# driver_V1_2.net
KiCad netlist of a schematic drawn in Altium Designer
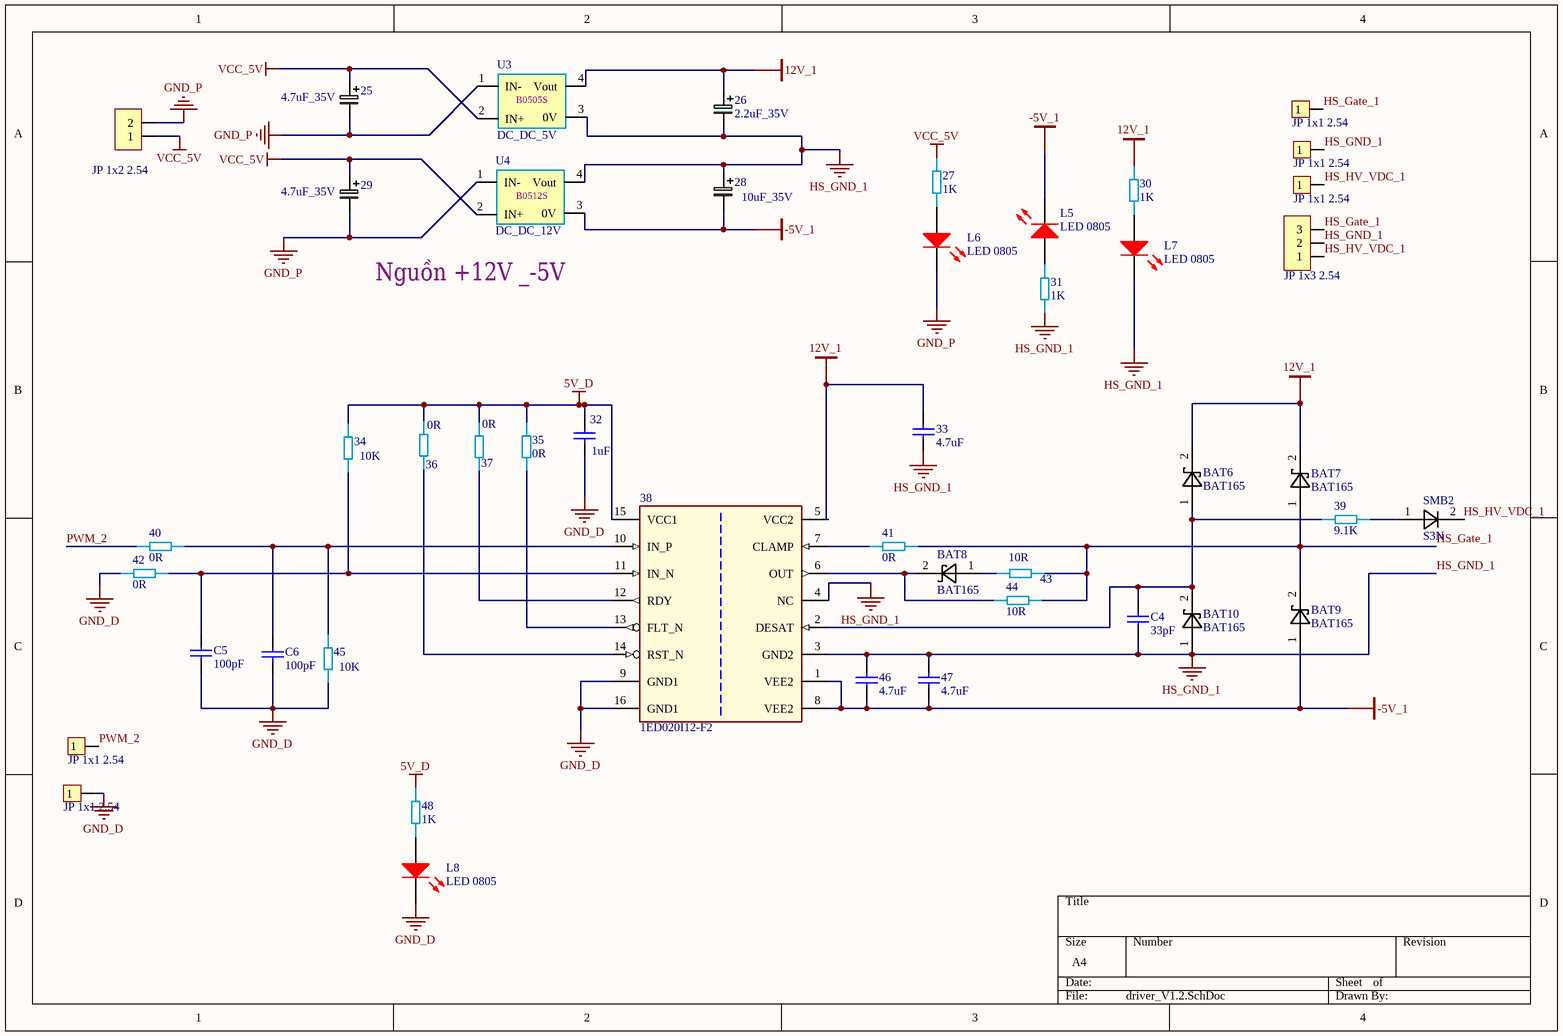
[diagram p0: driver_V1.2.SchDoc]

(export (version "E")
  (design (tool "Eeschema 10.0.6"))
  (components
    (comp (ref "25")
      (value "4.7uF_35V")
      (footprint "tu_4x5.4mm")
      (description "capacitor_electric")
      (libsource (lib "labari_altium1") (part "capacitor_electric"))
    )
    (comp (ref "26")
      (value "2.2uF_35V")
      (footprint "tu_4x5.4mm")
      (description "capacitor_electric")
      (libsource (lib "labari_altium1") (part "capacitor_electric"))
    )
    (comp (ref "27")
      (value "1K")
      (footprint "RES1206")
      (libsource (lib "labari_altium1") (part "311-0.0GRTR-ND"))
    )
    (comp (ref "28")
      (value "10uF_35V")
      (footprint "tu_4x5.4mm")
      (description "capacitor_electric")
      (libsource (lib "labari_altium1") (part "capacitor_electric"))
    )
    (comp (ref "29")
      (value "4.7uF_35V")
      (footprint "tu_4x5.4mm")
      (description "capacitor_electric")
      (libsource (lib "labari_altium1") (part "capacitor_electric"))
    )
    (comp (ref "30")
      (value "1K")
      (footprint "RES1206")
      (libsource (lib "labari_altium1") (part "311-0.0GRTR-ND"))
    )
    (comp (ref "31")
      (value "1K")
      (footprint "RES1206")
      (libsource (lib "labari_altium1") (part "311-0.0GRTR-ND"))
    )
    (comp (ref "32")
      (value "1uF")
      (footprint "Tu 0805_N")
      (libsource (lib "labari_altium1") (part "cap_0805"))
    )
    (comp (ref "33")
      (value "4.7uF")
      (footprint "tu 1206_N")
      (libsource (lib "labari_altium1") (part "cap_1210"))
    )
    (comp (ref "34")
      (value "10K")
      (footprint "RES1206")
      (libsource (lib "labari_altium1") (part "311-0.0GRTR-ND"))
    )
    (comp (ref "35")
      (value "0R")
      (footprint "RES1206")
      (libsource (lib "labari_altium1") (part "311-0.0GRTR-ND"))
    )
    (comp (ref "36")
      (value "0R")
      (footprint "RES1206")
      (libsource (lib "labari_altium1") (part "311-0.0GRTR-ND"))
    )
    (comp (ref "37")
      (value "0R")
      (footprint "RES1206")
      (libsource (lib "labari_altium1") (part "311-0.0GRTR-ND"))
    )
    (comp (ref "38")
      (value "1ED020I12-F2")
      (footprint "SOIC127P1028X264-16N-1")
      (description "Single IGBT Driver IC")
      (fields (field (name "MANUFACTURER") "Infineon Technologies"))
      (libsource (lib "labari_altium1") (part "1ED020I12-F2"))
    )
    (comp (ref "39")
      (value "9.1K")
      (footprint "RES_2512")
      (libsource (lib "labari_altium1") (part "311-0.0GRTR-ND"))
    )
    (comp (ref "40")
      (value "0R")
      (footprint "RES1206")
      (libsource (lib "labari_altium1") (part "311-0.0GRTR-ND"))
    )
    (comp (ref "41")
      (value "0R")
      (footprint "RES_2512")
      (libsource (lib "labari_altium1") (part "311-0.0GRTR-ND"))
    )
    (comp (ref "42")
      (value "0R")
      (footprint "RES1206")
      (libsource (lib "labari_altium1") (part "311-0.0GRTR-ND"))
    )
    (comp (ref "43")
      (value "10R")
      (footprint "RES_2512")
      (libsource (lib "labari_altium1") (part "311-0.0GRTR-ND"))
    )
    (comp (ref "44")
      (value "10R")
      (footprint "RES_2512")
      (libsource (lib "labari_altium1") (part "311-0.0GRTR-ND"))
    )
    (comp (ref "45")
      (value "10K")
      (footprint "RES1206")
      (libsource (lib "labari_altium1") (part "311-0.0GRTR-ND"))
    )
    (comp (ref "46")
      (value "4.7uF")
      (footprint "tu 1206_N")
      (libsource (lib "labari_altium1") (part "cap_1210"))
    )
    (comp (ref "47")
      (value "4.7uF")
      (footprint "tu 1206_N")
      (libsource (lib "labari_altium1") (part "cap_1210"))
    )
    (comp (ref "48")
      (value "1K")
      (footprint "RES1206")
      (libsource (lib "labari_altium1") (part "311-0.0GRTR-ND"))
    )
    (comp (ref "BAT6") (value "BAT165") (footprint "SMB") (libsource (lib "labari_altium1") (part "BAT165")))
    (comp (ref "BAT7") (value "BAT165") (footprint "SMB") (libsource (lib "labari_altium1") (part "BAT165")))
    (comp (ref "BAT8") (value "BAT165") (footprint "SMB") (libsource (lib "labari_altium1") (part "BAT165")))
    (comp (ref "BAT9") (value "BAT165") (footprint "SMB") (libsource (lib "labari_altium1") (part "BAT165")))
    (comp (ref "BAT10") (value "BAT165") (footprint "SMB") (libsource (lib "labari_altium1") (part "BAT165")))
    (comp (ref "C4")
      (value "33pF")
      (footprint "Tu 0805_N")
      (libsource (lib "labari_altium1") (part "cap_0805"))
    )
    (comp (ref "C5")
      (value "100pF")
      (footprint "Tu 0805_N")
      (libsource (lib "labari_altium1") (part "cap_0805"))
    )
    (comp (ref "C6")
      (value "100pF")
      (footprint "Tu 0805_N")
      (libsource (lib "labari_altium1") (part "cap_0805"))
    )
    (comp (ref "JP9")
      (value "JP 1x1 2.54")
      (footprint "test_point")
      (description "Cắm")
      (libsource (lib "labari_altium1") (part "JP 1x1 2.54 Duc Thang"))
    )
    (comp (ref "JP10")
      (value "JP 1x2 2.54")
      (footprint "JP 1x2 DT_n")
      (description "Cắm")
      (libsource (lib "labari_altium1") (part "JP 1x2 2.54 Duc Thang"))
    )
    (comp (ref "JP11")
      (value "JP 1x1 2.54")
      (footprint "test_point")
      (description "Cắm")
      (libsource (lib "labari_altium1") (part "JP 1x1 2.54 Duc Thang"))
    )
    (comp (ref "JP12")
      (value "JP 1x1 2.54")
      (footprint "test_point")
      (description "Cắm")
      (libsource (lib "labari_altium1") (part "JP 1x1 2.54 Duc Thang"))
    )
    (comp (ref "JP13")
      (value "JP 1x3 2.54")
      (footprint "XH2.54M-3")
      (description "Cắm")
      (libsource (lib "labari_altium1") (part "JP 1x3 2.54 Duc Cong"))
    )
    (comp (ref "JP14")
      (value "JP 1x1 2.54")
      (footprint "test_point")
      (description "Cắm")
      (libsource (lib "labari_altium1") (part "JP 1x1 2.54 Duc Thang"))
    )
    (comp (ref "JP15")
      (value "JP 1x1 2.54")
      (footprint "test_point")
      (description "Cắm")
      (libsource (lib "labari_altium1") (part "JP 1x1 2.54 Duc Thang"))
    )
    (comp (ref "L5")
      (value "LED 0805")
      (footprint "LED-0805-Red")
      (description "Dán")
      (libsource (lib "labari_altium1") (part "LED 0805 Do"))
    )
    (comp (ref "L6")
      (value "LED 0805")
      (footprint "LED-0805-Red")
      (description "Dán")
      (libsource (lib "labari_altium1") (part "LED 0805 Do"))
    )
    (comp (ref "L7")
      (value "LED 0805")
      (footprint "LED-0805-Red")
      (description "Dán")
      (libsource (lib "labari_altium1") (part "LED 0805 Do"))
    )
    (comp (ref "L8")
      (value "LED 0805")
      (footprint "LED-0805-Red")
      (description "Dán")
      (libsource (lib "labari_altium1") (part "LED 0805 Do"))
    )
    (comp (ref "SMB2") (value "S3N") (footprint "SMB") (libsource (lib "labari_altium1") (part "S3A-S3N")))
    (comp (ref "U3")
      (value "DC_DC_5V")
      (footprint "B0505S/D-1W")
      (libsource (lib "labari_altium1") (part "DC_DC_5v"))
    )
    (comp (ref "U4")
      (value "DC_DC_12V")
      (footprint "B0512S/D-1W")
      (libsource (lib "labari_altium1") (part "DC_DC_12v"))
    )
  )
  (nets
    (net (code "1") (name "-5V_1") (class "Default")
      (node (ref "28") (pin "2") (pinfunction "2_2") (pintype "passive"))
      (node (ref "38") (pin "1") (pinfunction "VEE2_1") (pintype "power_in"))
      (node (ref "38") (pin "8") (pinfunction "VEE2_8") (pintype "power_in"))
      (node (ref "46") (pin "1") (pinfunction "1_1") (pintype "passive"))
      (node (ref "47") (pin "1") (pinfunction "1_1") (pintype "passive"))
      (node (ref "BAT9") (pin "1") (pinfunction "1_1") (pintype "passive"))
      (node (ref "L5") (pin "2") (pinfunction "K_2") (pintype "passive"))
      (node (ref "U4") (pin "3") (pinfunction "0V_3") (pintype "passive"))
    )
    (net (code "2") (name "/HS_Gate_1") (class "Default")
      (node (ref "41") (pin "2") (pinfunction "2_2") (pintype "passive"))
      (node (ref "43") (pin "2") (pinfunction "2_2") (pintype "passive"))
      (node (ref "44") (pin "2") (pinfunction "2_2") (pintype "passive"))
      (node (ref "BAT7") (pin "1") (pinfunction "1_1") (pintype "passive"))
      (node (ref "BAT9") (pin "2") (pinfunction "2_2") (pintype "passive"))
      (node (ref "JP13") (pin "3") (pinfunction "3_3") (pintype "passive"))
      (node (ref "JP9") (pin "1") (pinfunction "1_1") (pintype "passive"))
    )
    (net (code "3") (name "/HS_HV_VDC_1") (class "Default")
      (node (ref "JP12") (pin "1") (pinfunction "1_1") (pintype "passive"))
      (node (ref "JP13") (pin "1") (pinfunction "1_1") (pintype "passive"))
      (node (ref "SMB2") (pin "2") (pinfunction "2_2") (pintype "passive"))
    )
    (net (code "4") (name "/PWM_2") (class "Default")
      (node (ref "40") (pin "2") (pinfunction "2_2") (pintype "passive"))
      (node (ref "JP14") (pin "1") (pinfunction "1_1") (pintype "passive"))
    )
    (net (code "5") (name "5V_D") (class "Default")
      (node (ref "32") (pin "2") (pinfunction "2_2") (pintype "passive"))
      (node (ref "34") (pin "2") (pinfunction "2_2") (pintype "passive"))
      (node (ref "35") (pin "1") (pinfunction "1_1") (pintype "passive"))
      (node (ref "36") (pin "2") (pinfunction "2_2") (pintype "passive"))
      (node (ref "37") (pin "1") (pinfunction "1_1") (pintype "passive"))
      (node (ref "38") (pin "15") (pinfunction "VCC1_15") (pintype "power_in"))
      (node (ref "48") (pin "1") (pinfunction "1_1") (pintype "passive"))
    )
    (net (code "6") (name "12V_1") (class "Default")
      (node (ref "26") (pin "1") (pinfunction "1_1") (pintype "passive"))
      (node (ref "30") (pin "1") (pinfunction "1_1") (pintype "passive"))
      (node (ref "33") (pin "2") (pinfunction "2_2") (pintype "passive"))
      (node (ref "38") (pin "5") (pinfunction "VCC2_5") (pintype "power_in"))
      (node (ref "BAT6") (pin "2") (pinfunction "2_2") (pintype "passive"))
      (node (ref "BAT7") (pin "2") (pinfunction "2_2") (pintype "passive"))
      (node (ref "U3") (pin "4") (pinfunction "Vout_4") (pintype "passive"))
    )
    (net (code "7") (name "GND_D") (class "Default")
      (node (ref "32") (pin "1") (pinfunction "1_1") (pintype "passive"))
      (node (ref "38") (pin "16") (pinfunction "GND1_16") (pintype "power_in"))
      (node (ref "38") (pin "9") (pinfunction "GND1_9") (pintype "power_in"))
      (node (ref "42") (pin "2") (pinfunction "2_2") (pintype "passive"))
      (node (ref "45") (pin "1") (pinfunction "1_1") (pintype "passive"))
      (node (ref "C5") (pin "1") (pinfunction "1_1") (pintype "passive"))
      (node (ref "C6") (pin "1") (pinfunction "1_1") (pintype "passive"))
      (node (ref "JP15") (pin "1") (pinfunction "1_1") (pintype "passive"))
      (node (ref "L8") (pin "2") (pinfunction "K_2") (pintype "passive"))
    )
    (net (code "8") (name "GND_P") (class "Default")
      (node (ref "25") (pin "2") (pinfunction "2_2") (pintype "passive"))
      (node (ref "29") (pin "2") (pinfunction "2_2") (pintype "passive"))
      (node (ref "JP10") (pin "2") (pinfunction "2_2") (pintype "passive"))
      (node (ref "L6") (pin "2") (pinfunction "K_2") (pintype "passive"))
      (node (ref "U3") (pin "1") (pinfunction "IN-_1") (pintype "passive"))
      (node (ref "U4") (pin "1") (pinfunction "IN-_1") (pintype "passive"))
    )
    (net (code "9") (name "HS_GND_1") (class "Default")
      (node (ref "26") (pin "2") (pinfunction "2_2") (pintype "passive"))
      (node (ref "28") (pin "1") (pinfunction "1_1") (pintype "passive"))
      (node (ref "31") (pin "2") (pinfunction "2_2") (pintype "passive"))
      (node (ref "33") (pin "1") (pinfunction "1_1") (pintype "passive"))
      (node (ref "38") (pin "3") (pinfunction "GND2_3") (pintype "power_in"))
      (node (ref "38") (pin "4") (pinfunction "NC_4") (pintype "passive"))
      (node (ref "46") (pin "2") (pinfunction "2_2") (pintype "passive"))
      (node (ref "47") (pin "2") (pinfunction "2_2") (pintype "passive"))
      (node (ref "BAT10") (pin "1") (pinfunction "1_1") (pintype "passive"))
      (node (ref "C4") (pin "1") (pinfunction "1_1") (pintype "passive"))
      (node (ref "JP11") (pin "1") (pinfunction "1_1") (pintype "passive"))
      (node (ref "JP13") (pin "2") (pinfunction "2_2") (pintype "passive"))
      (node (ref "L7") (pin "2") (pinfunction "K_2") (pintype "passive"))
      (node (ref "U3") (pin "3") (pinfunction "0V_3") (pintype "passive"))
      (node (ref "U4") (pin "4") (pinfunction "Vout_4") (pintype "passive"))
    )
    (net (code "10") (name "Net-(38-CLAMP)") (class "Default")
      (node (ref "38") (pin "7") (pinfunction "CLAMP_7") (pintype "input"))
      (node (ref "41") (pin "1") (pinfunction "1_1") (pintype "passive"))
    )
    (net (code "11") (name "Net-(38-DESAT)") (class "Default")
      (node (ref "38") (pin "2") (pinfunction "DESAT_2") (pintype "input"))
      (node (ref "39") (pin "1") (pinfunction "1_1") (pintype "passive"))
      (node (ref "BAT10") (pin "2") (pinfunction "2_2") (pintype "passive"))
      (node (ref "BAT6") (pin "1") (pinfunction "1_1") (pintype "passive"))
      (node (ref "C4") (pin "2") (pinfunction "2_2") (pintype "passive"))
    )
    (net (code "12") (name "Net-(38-FLT_N)") (class "Default")
      (node (ref "35") (pin "2") (pinfunction "2_2") (pintype "passive"))
      (node (ref "38") (pin "13") (pinfunction "FLT_N_13") (pintype "output"))
    )
    (net (code "13") (name "Net-(38-IN_N)") (class "Default")
      (node (ref "34") (pin "1") (pinfunction "1_1") (pintype "passive"))
      (node (ref "38") (pin "11") (pinfunction "IN_N_11") (pintype "input"))
      (node (ref "42") (pin "1") (pinfunction "1_1") (pintype "passive"))
      (node (ref "C5") (pin "2") (pinfunction "2_2") (pintype "passive"))
    )
    (net (code "14") (name "Net-(38-IN_P)") (class "Default")
      (node (ref "38") (pin "10") (pinfunction "IN_P_10") (pintype "input"))
      (node (ref "40") (pin "1") (pinfunction "1_1") (pintype "passive"))
      (node (ref "45") (pin "2") (pinfunction "2_2") (pintype "passive"))
      (node (ref "C6") (pin "2") (pinfunction "2_2") (pintype "passive"))
    )
    (net (code "15") (name "Net-(38-OUT)") (class "Default")
      (node (ref "38") (pin "6") (pinfunction "OUT_6") (pintype "output"))
      (node (ref "44") (pin "1") (pinfunction "1_1") (pintype "passive"))
      (node (ref "BAT8") (pin "2") (pinfunction "2_2") (pintype "passive"))
    )
    (net (code "16") (name "Net-(38-RDY)") (class "Default")
      (node (ref "37") (pin "2") (pinfunction "2_2") (pintype "passive"))
      (node (ref "38") (pin "12") (pinfunction "RDY_12") (pintype "output"))
    )
    (net (code "17") (name "Net-(38-RST_N)") (class "Default")
      (node (ref "36") (pin "1") (pinfunction "1_1") (pintype "passive"))
      (node (ref "38") (pin "14") (pinfunction "RST_N_14") (pintype "input"))
    )
    (net (code "18") (name "Net-(39-Pad2)") (class "Default")
      (node (ref "39") (pin "2") (pinfunction "2_2") (pintype "passive"))
      (node (ref "SMB2") (pin "1") (pinfunction "1_1") (pintype "passive"))
    )
    (net (code "19") (name "Net-(43-Pad1)") (class "Default")
      (node (ref "43") (pin "1") (pinfunction "1_1") (pintype "passive"))
      (node (ref "BAT8") (pin "1") (pinfunction "1_1") (pintype "passive"))
    )
    (net (code "20") (name "Net-(L5-A)") (class "Default")
      (node (ref "31") (pin "1") (pinfunction "1_1") (pintype "passive"))
      (node (ref "L5") (pin "1") (pinfunction "A_1") (pintype "passive"))
    )
    (net (code "21") (name "Net-(L6-A)") (class "Default")
      (node (ref "27") (pin "2") (pinfunction "2_2") (pintype "passive"))
      (node (ref "L6") (pin "1") (pinfunction "A_1") (pintype "passive"))
    )
    (net (code "22") (name "Net-(L7-A)") (class "Default")
      (node (ref "30") (pin "2") (pinfunction "2_2") (pintype "passive"))
      (node (ref "L7") (pin "1") (pinfunction "A_1") (pintype "passive"))
    )
    (net (code "23") (name "Net-(L8-A)") (class "Default")
      (node (ref "48") (pin "2") (pinfunction "2_2") (pintype "passive"))
      (node (ref "L8") (pin "1") (pinfunction "A_1") (pintype "passive"))
    )
    (net (code "24") (name "VCC_5V") (class "Default")
      (node (ref "25") (pin "1") (pinfunction "1_1") (pintype "passive"))
      (node (ref "27") (pin "1") (pinfunction "1_1") (pintype "passive"))
      (node (ref "29") (pin "1") (pinfunction "1_1") (pintype "passive"))
      (node (ref "JP10") (pin "1") (pinfunction "1_1") (pintype "passive"))
      (node (ref "U3") (pin "2") (pinfunction "IN+_2") (pintype "passive"))
      (node (ref "U4") (pin "2") (pinfunction "IN+_2") (pintype "passive"))
    )
  )
)
